# bdclock.net
KiCad netlist of a schematic drawn in EAGLE
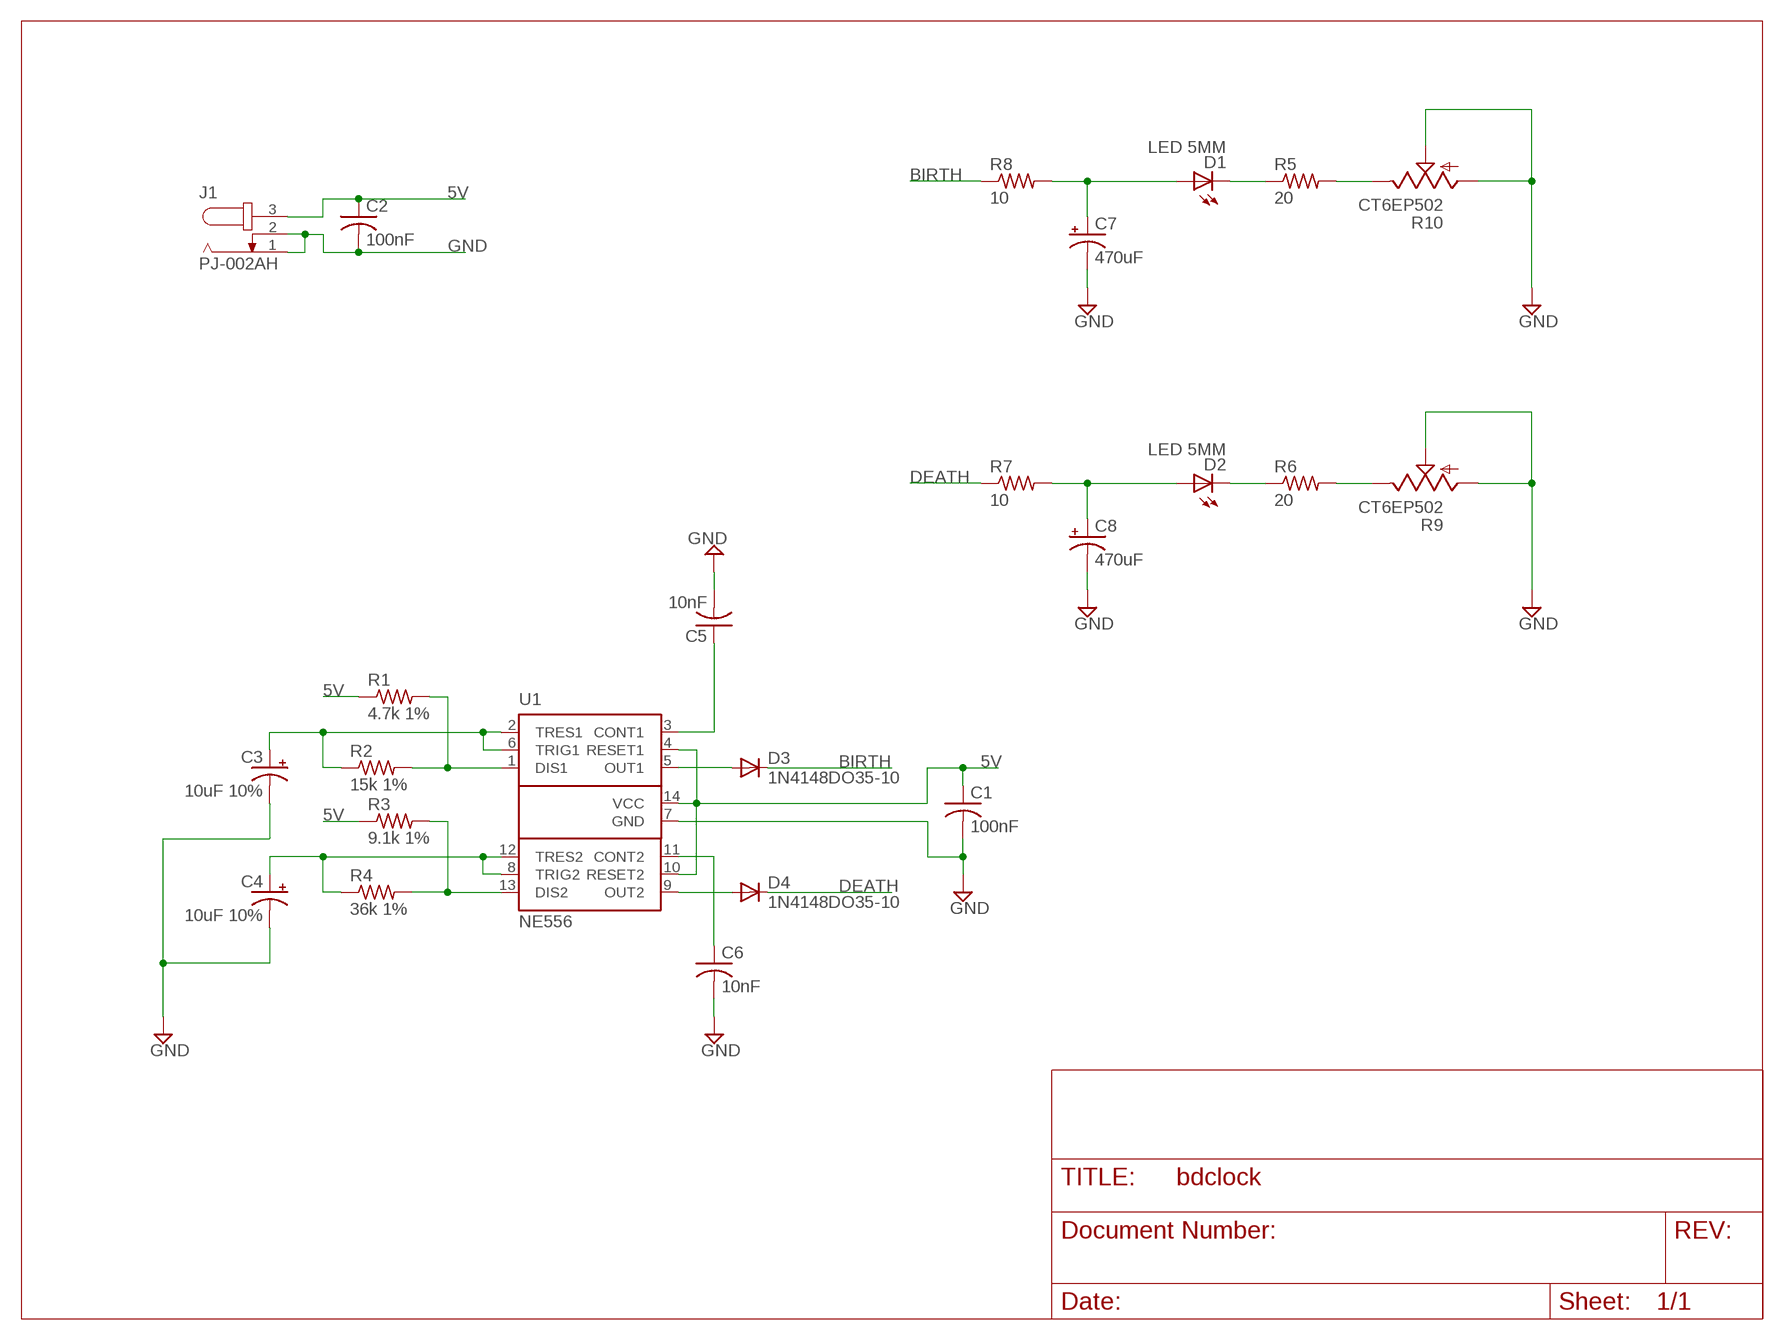
[diagram p0: schematic, sheet 1]

(export (version "E")
  (design (tool "Eeschema 10.0.6"))
  (components
    (comp (ref "C1")
      (value "100nF")
      (footprint "eagle-import:C025-025X050")
      (libsource (lib "eagle-import") (part "C-US025-025X050"))
    )
    (comp (ref "C2")
      (value "100nF")
      (footprint "eagle-import:C025-025X050")
      (libsource (lib "eagle-import") (part "C-US025-025X050"))
    )
    (comp (ref "C3")
      (value "10uF 10%")
      (footprint "eagle-import:E2-5")
      (libsource (lib "eagle-import") (part "CPOL-USE2-5"))
    )
    (comp (ref "C4")
      (value "10uF 10%")
      (footprint "eagle-import:E2-5")
      (libsource (lib "eagle-import") (part "CPOL-USE2-5"))
    )
    (comp (ref "C5")
      (value "10nF")
      (footprint "eagle-import:C025-024X044")
      (libsource (lib "eagle-import") (part "C-US025-024X044"))
    )
    (comp (ref "C6")
      (value "10nF")
      (footprint "eagle-import:C025-024X044")
      (libsource (lib "eagle-import") (part "C-US025-024X044"))
    )
    (comp (ref "C7")
      (value "470uF")
      (footprint "eagle-import:E2,5-6")
      (libsource (lib "eagle-import") (part "CPOL-USE2.5-6"))
    )
    (comp (ref "C8")
      (value "470uF")
      (footprint "eagle-import:E2,5-6")
      (libsource (lib "eagle-import") (part "CPOL-USE2.5-6"))
    )
    (comp (ref "D1")
      (value "LED 5MM")
      (footprint "eagle-import:LED5MM")
      (libsource (lib "eagle-import") (part "LED5MM"))
    )
    (comp (ref "D2")
      (value "LED 5MM")
      (footprint "eagle-import:LED5MM")
      (libsource (lib "eagle-import") (part "LED5MM"))
    )
    (comp (ref "D3")
      (value "1N4148DO35-10")
      (footprint "eagle-import:DO35-10")
      (libsource (lib "eagle-import") (part "1N4148DO35-10"))
    )
    (comp (ref "D4")
      (value "1N4148DO35-10")
      (footprint "eagle-import:DO35-10")
      (libsource (lib "eagle-import") (part "1N4148DO35-10"))
    )
    (comp (ref "J1")
      (value "PJ-002AH")
      (footprint "eagle-import:SPC4077")
      (libsource (lib "eagle-import") (part "JACK-PLUG0"))
    )
    (comp (ref "R1")
      (value "4.7k 1%")
      (footprint "eagle-import:0207_10")
      (libsource (lib "eagle-import") (part "R-US_0207/10"))
    )
    (comp (ref "R2")
      (value "15k 1%")
      (footprint "eagle-import:0207_10")
      (libsource (lib "eagle-import") (part "R-US_0207/10"))
    )
    (comp (ref "R3")
      (value "9.1k 1%")
      (footprint "eagle-import:0207_10")
      (libsource (lib "eagle-import") (part "R-US_0207/10"))
    )
    (comp (ref "R4")
      (value "36k 1%")
      (footprint "eagle-import:0207_10")
      (libsource (lib "eagle-import") (part "R-US_0207/10"))
    )
    (comp (ref "R5")
      (value "20")
      (footprint "eagle-import:0207_10")
      (libsource (lib "eagle-import") (part "R-US_0207/10"))
    )
    (comp (ref "R6")
      (value "20")
      (footprint "eagle-import:0207_10")
      (libsource (lib "eagle-import") (part "R-US_0207/10"))
    )
    (comp (ref "R7")
      (value "10")
      (footprint "eagle-import:0207_10")
      (libsource (lib "eagle-import") (part "R-US_0207/10"))
    )
    (comp (ref "R8")
      (value "10")
      (footprint "eagle-import:0207_10")
      (libsource (lib "eagle-import") (part "R-US_0207/10"))
    )
    (comp (ref "R9")
      (value "CT6EP502")
      (footprint "eagle-import:CT6")
      (libsource (lib "eagle-import") (part "TRIM_US-CT6"))
    )
    (comp (ref "R10")
      (value "CT6EP502")
      (footprint "eagle-import:CT6")
      (libsource (lib "eagle-import") (part "TRIM_US-CT6"))
    )
    (comp (ref "U1")
      (value "NE556")
      (footprint "eagle-import:DIL14")
      (libsource (lib "eagle-import") (part "NE556"))
    )
  )
  (nets
    (net (code "1") (name "/5V") (class "Default")
      (node (ref "C1") (pin "1") (pinfunction "1_1") (pintype "passive"))
      (node (ref "C2") (pin "1") (pinfunction "1_1") (pintype "passive"))
      (node (ref "J1") (pin "3") (pinfunction "3_3") (pintype "passive"))
      (node (ref "R1") (pin "1") (pinfunction "1_1") (pintype "passive"))
      (node (ref "R3") (pin "1") (pinfunction "1_1") (pintype "passive"))
      (node (ref "U1") (pin "10") (pinfunction "RESET2_10") (pintype "input"))
      (node (ref "U1") (pin "14") (pinfunction "VCC_14") (pintype "power_in"))
      (node (ref "U1") (pin "4") (pinfunction "RESET1_4") (pintype "input"))
    )
    (net (code "2") (name "/BIRTH") (class "Default")
      (node (ref "D3") (pin "C") (pinfunction "C_C") (pintype "passive"))
      (node (ref "R8") (pin "1") (pinfunction "1_1") (pintype "passive"))
    )
    (net (code "3") (name "/DEATH") (class "Default")
      (node (ref "D4") (pin "C") (pinfunction "C_C") (pintype "passive"))
      (node (ref "R7") (pin "1") (pinfunction "1_1") (pintype "passive"))
    )
    (net (code "4") (name "GND") (class "Default")
      (node (ref "C1") (pin "2") (pinfunction "2_2") (pintype "passive"))
      (node (ref "C2") (pin "2") (pinfunction "2_2") (pintype "passive"))
      (node (ref "C3") (pin "-") (pinfunction "-_-") (pintype "passive"))
      (node (ref "C4") (pin "-") (pinfunction "-_-") (pintype "passive"))
      (node (ref "C5") (pin "2") (pinfunction "2_2") (pintype "passive"))
      (node (ref "C6") (pin "2") (pinfunction "2_2") (pintype "passive"))
      (node (ref "C7") (pin "-") (pinfunction "-_-") (pintype "passive"))
      (node (ref "C8") (pin "-") (pinfunction "-_-") (pintype "passive"))
      (node (ref "J1") (pin "1") (pinfunction "1_1") (pintype "passive"))
      (node (ref "J1") (pin "2") (pinfunction "2_2") (pintype "passive"))
      (node (ref "R10") (pin "A") (pinfunction "A_A") (pintype "passive"))
      (node (ref "R10") (pin "S") (pinfunction "S_S") (pintype "passive"))
      (node (ref "R9") (pin "A") (pinfunction "A_A") (pintype "passive"))
      (node (ref "R9") (pin "S") (pinfunction "S_S") (pintype "passive"))
      (node (ref "U1") (pin "7") (pinfunction "GND_7") (pintype "power_in"))
    )
    (net (code "5") (name "Net-(C7-Pad+)") (class "Default")
      (node (ref "C7") (pin "+") (pinfunction "+_+") (pintype "passive"))
      (node (ref "D1") (pin "A") (pinfunction "A_A") (pintype "passive"))
      (node (ref "R8") (pin "2") (pinfunction "2_2") (pintype "passive"))
    )
    (net (code "6") (name "Net-(C8-Pad+)") (class "Default")
      (node (ref "C8") (pin "+") (pinfunction "+_+") (pintype "passive"))
      (node (ref "D2") (pin "A") (pinfunction "A_A") (pintype "passive"))
      (node (ref "R7") (pin "2") (pinfunction "2_2") (pintype "passive"))
    )
    (net (code "7") (name "Net-(D1-C)") (class "Default")
      (node (ref "D1") (pin "K") (pinfunction "C_K") (pintype "passive"))
      (node (ref "R5") (pin "1") (pinfunction "1_1") (pintype "passive"))
    )
    (net (code "8") (name "Net-(D2-C)") (class "Default")
      (node (ref "D2") (pin "K") (pinfunction "C_K") (pintype "passive"))
      (node (ref "R6") (pin "1") (pinfunction "1_1") (pintype "passive"))
    )
    (net (code "9") (name "Net-(R6-Pad2)") (class "Default")
      (node (ref "R6") (pin "2") (pinfunction "2_2") (pintype "passive"))
      (node (ref "R9") (pin "E") (pinfunction "E_E") (pintype "passive"))
    )
    (net (code "10") (name "Net-(R10-PadE)") (class "Default")
      (node (ref "R10") (pin "E") (pinfunction "E_E") (pintype "passive"))
      (node (ref "R5") (pin "2") (pinfunction "2_2") (pintype "passive"))
    )
    (net (code "11") (name "Net-(U1-CONT1)") (class "Default")
      (node (ref "C5") (pin "1") (pinfunction "1_1") (pintype "passive"))
      (node (ref "U1") (pin "3") (pinfunction "CONT1_3") (pintype "input"))
    )
    (net (code "12") (name "Net-(U1-CONT2)") (class "Default")
      (node (ref "C6") (pin "1") (pinfunction "1_1") (pintype "passive"))
      (node (ref "U1") (pin "11") (pinfunction "CONT2_11") (pintype "input"))
    )
    (net (code "13") (name "Net-(U1-DIS1)") (class "Default")
      (node (ref "R1") (pin "2") (pinfunction "2_2") (pintype "passive"))
      (node (ref "R2") (pin "2") (pinfunction "2_2") (pintype "passive"))
      (node (ref "U1") (pin "1") (pinfunction "DIS1_1") (pintype "input"))
    )
    (net (code "14") (name "Net-(U1-DIS2)") (class "Default")
      (node (ref "R3") (pin "2") (pinfunction "2_2") (pintype "passive"))
      (node (ref "R4") (pin "2") (pinfunction "2_2") (pintype "passive"))
      (node (ref "U1") (pin "13") (pinfunction "DIS2_13") (pintype "input"))
    )
    (net (code "15") (name "Net-(U1-OUT1)") (class "Default")
      (node (ref "D3") (pin "A") (pinfunction "A_A") (pintype "passive"))
      (node (ref "U1") (pin "5") (pinfunction "OUT1_5") (pintype "output"))
    )
    (net (code "16") (name "Net-(U1-OUT2)") (class "Default")
      (node (ref "D4") (pin "A") (pinfunction "A_A") (pintype "passive"))
      (node (ref "U1") (pin "9") (pinfunction "OUT2_9") (pintype "output"))
    )
    (net (code "17") (name "Net-(U1-TRES1)") (class "Default")
      (node (ref "C3") (pin "+") (pinfunction "+_+") (pintype "passive"))
      (node (ref "R2") (pin "1") (pinfunction "1_1") (pintype "passive"))
      (node (ref "U1") (pin "2") (pinfunction "TRES1_2") (pintype "input"))
      (node (ref "U1") (pin "6") (pinfunction "TRIG1_6") (pintype "input"))
    )
    (net (code "18") (name "Net-(U1-TRES2)") (class "Default")
      (node (ref "C4") (pin "+") (pinfunction "+_+") (pintype "passive"))
      (node (ref "R4") (pin "1") (pinfunction "1_1") (pintype "passive"))
      (node (ref "U1") (pin "12") (pinfunction "TRES2_12") (pintype "input"))
      (node (ref "U1") (pin "8") (pinfunction "TRIG2_8") (pintype "input"))
    )
  )
)
